# Sheet1.net
KiCad netlist of a schematic drawn in Altium Designer
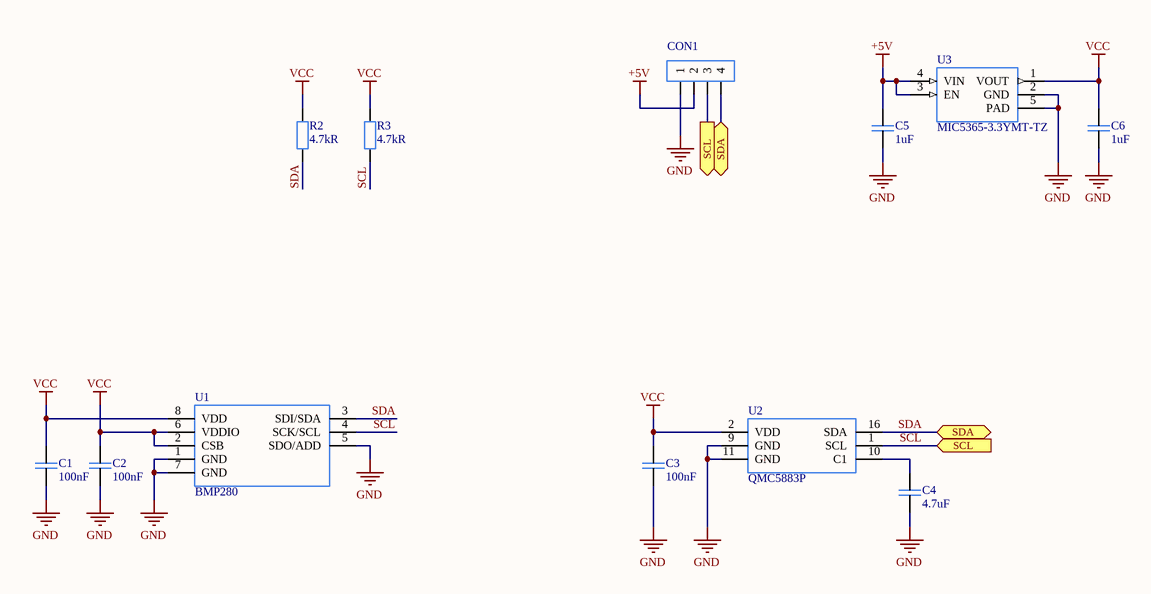
[diagram p0: Sheet1.SchDoc]

(export (version "E")
  (design (tool "Eeschema 10.0.6"))
  (components
    (comp (ref "C1")
      (value "100nF")
      (footprint "C0201_M")
      (description "Cap Ceramic 0.1uF 25V X5R 10% SMD 0201 85°C Paper T/R")
      (fields
        (field (name "MANUFACTURER") "Yageo")
        (field (name "MANUFACTURER PART NUMBER") "CC0201KRX5R8BB104")
      )
      (libsource (lib "Schlib1") (part "Capacitor"))
    )
    (comp (ref "C2")
      (value "100nF")
      (footprint "C0201_M")
      (description "Cap Ceramic 0.1uF 25V X5R 10% SMD 0201 85°C Paper T/R")
      (fields
        (field (name "MANUFACTURER") "Yageo")
        (field (name "MANUFACTURER PART NUMBER") "CC0201KRX5R8BB104")
      )
      (libsource (lib "Schlib1") (part "Capacitor"))
    )
    (comp (ref "C3")
      (value "100nF")
      (footprint "C0201_M")
      (description "Cap Ceramic 0.1uF 25V X5R 10% SMD 0201 85°C Paper T/R")
      (fields
        (field (name "MANUFACTURER") "Yageo")
        (field (name "MANUFACTURER PART NUMBER") "CC0201KRX5R8BB104")
      )
      (libsource (lib "Schlib1") (part "Capacitor"))
    )
    (comp (ref "C4")
      (value "4.7uF")
      (footprint "C0402_N")
      (description "贴片电容（MLCC） 0402")
      (fields
        (field (name "MANUFACTURER") "Taiyo Yuden")
        (field (name "MANUFACTURER PART NUMBER") "EDK105BBJ475MVLF")
      )
      (libsource (lib "Schlib1") (part "Capacitor"))
    )
    (comp (ref "C5")
      (value "1uF")
      (footprint "C0201_M")
      (description "Cap Cer 1UF 10V X5R 0201")
      (fields
        (field (name "MANUFACTURER") "Kyocera AVX")
        (field (name "MANUFACTURE PART NUMBER") "CM03X5R105M10AH")
      )
      (libsource (lib "Schlib1") (part "Capacitor"))
    )
    (comp (ref "C6")
      (value "1uF")
      (footprint "C0201_M")
      (description "Cap Cer 1UF 10V X5R 0201")
      (fields
        (field (name "MANUFACTURER") "Kyocera AVX")
        (field (name "MANUFACTURE PART NUMBER") "CM03X5R105M10AH")
      )
      (libsource (lib "Schlib1") (part "Capacitor"))
    )
    (comp (ref "CON1")
      (value "Header 4")
      (footprint "HEADER-4-2mm")
      (description "Connector; Header; 4pin")
      (libsource (lib "Schlib1") (part "HEADER1X4"))
    )
    (comp (ref "R2")
      (value "4.7kR")
      (footprint "R0201_L")
      (description "Res Thick Film 0201 4.7K Ohm 1% 1/20W ±200ppm/°C Molded SMD SMD Paper T/R")
      (fields
        (field (name "MANUFACTURER") "Yageo")
        (field (name "MANUFACTURER PART NUMBER") "RC0201FR-074K7L")
      )
      (libsource (lib "Schlib1") (part "Resistor_EU"))
    )
    (comp (ref "R3")
      (value "4.7kR")
      (footprint "R0201_L")
      (description "Res Thick Film 0201 4.7K Ohm 1% 1/20W ±200ppm/°C Molded SMD SMD Paper T/R")
      (fields
        (field (name "MANUFACTURER") "Yageo")
        (field (name "MANUFACTURER PART NUMBER") "RC0201FR-074K7L")
      )
      (libsource (lib "Schlib1") (part "Resistor_EU"))
    )
    (comp (ref "U1")
      (value "BMP280")
      (footprint "LGA-8")
      (description "SENSOR PRESSURE ABS")
      (fields (field (name "MANUFACTURER") "Bosch"))
      (libsource (lib "Schlib1") (part "BMP280"))
    )
    (comp (ref "U2")
      (value "QMC5883P")
      (footprint "LGA-16_3X3")
      (libsource (lib "Schlib1") (part "QMC5883P"))
    )
    (comp (ref "U3")
      (value "MIC5365-3.3YMT-TZ")
      (footprint "UDFN-4")
      (description "MIC5365 Series 3.3 V Fixed Output 150 mA Surface Mount LDO Regulator - TMLF-4")
      (fields (field (name "MANUFACTURER") "Microchip"))
      (libsource (lib "Schlib1") (part "MIC5365-3.3YMT-TZ"))
    )
  )
  (nets
    (net (code "1") (name "+5V") (class "Default")
      (node (ref "C5") (pin "1") (pinfunction "1_1") (pintype "passive"))
      (node (ref "CON1") (pin "2") (pinfunction "2_2") (pintype "passive"))
      (node (ref "U3") (pin "3") (pinfunction "EN_3") (pintype "input"))
      (node (ref "U3") (pin "4") (pinfunction "VIN_4") (pintype "input"))
    )
    (net (code "2") (name "/SCL") (class "Default")
      (node (ref "CON1") (pin "3") (pinfunction "3_3") (pintype "passive"))
      (node (ref "R3") (pin "2") (pintype "passive"))
      (node (ref "U1") (pin "4") (pinfunction "SCK/SCL_4") (pintype "passive"))
      (node (ref "U2") (pin "1") (pinfunction "SCL_1") (pintype "passive"))
    )
    (net (code "3") (name "/SDA") (class "Default")
      (node (ref "CON1") (pin "4") (pinfunction "4_4") (pintype "passive"))
      (node (ref "R2") (pin "2") (pintype "passive"))
      (node (ref "U1") (pin "3") (pinfunction "SDI/SDA_3") (pintype "passive"))
      (node (ref "U2") (pin "16") (pinfunction "SDA_16") (pintype "passive"))
    )
    (net (code "4") (name "GND") (class "Default")
      (node (ref "C1") (pin "2") (pinfunction "2_2") (pintype "passive"))
      (node (ref "C2") (pin "1") (pinfunction "1_1") (pintype "passive"))
      (node (ref "C3") (pin "1") (pinfunction "1_1") (pintype "passive"))
      (node (ref "C4") (pin "2") (pinfunction "2_2") (pintype "passive"))
      (node (ref "C5") (pin "2") (pinfunction "2_2") (pintype "passive"))
      (node (ref "C6") (pin "2") (pinfunction "2_2") (pintype "passive"))
      (node (ref "CON1") (pin "1") (pinfunction "1_1") (pintype "passive"))
      (node (ref "U1") (pin "1") (pinfunction "GND_1") (pintype "passive"))
      (node (ref "U1") (pin "5") (pinfunction "SDO/ADD_5") (pintype "passive"))
      (node (ref "U1") (pin "7") (pinfunction "GND_7") (pintype "passive"))
      (node (ref "U2") (pin "11") (pinfunction "GND_11") (pintype "passive"))
      (node (ref "U2") (pin "9") (pinfunction "GND_9") (pintype "passive"))
      (node (ref "U3") (pin "2") (pinfunction "GND_2") (pintype "power_in"))
      (node (ref "U3") (pin "5") (pinfunction "PAD_5") (pintype "passive"))
    )
    (net (code "5") (name "Net-(U2-C1)") (class "Default")
      (node (ref "C4") (pin "1") (pinfunction "1_1") (pintype "passive"))
      (node (ref "U2") (pin "10") (pinfunction "C1_10") (pintype "passive"))
    )
    (net (code "6") (name "VCC") (class "Default")
      (node (ref "C1") (pin "1") (pinfunction "1_1") (pintype "passive"))
      (node (ref "C2") (pin "2") (pinfunction "2_2") (pintype "passive"))
      (node (ref "C3") (pin "2") (pinfunction "2_2") (pintype "passive"))
      (node (ref "C6") (pin "1") (pinfunction "1_1") (pintype "passive"))
      (node (ref "R2") (pin "1") (pintype "passive"))
      (node (ref "R3") (pin "1") (pintype "passive"))
      (node (ref "U1") (pin "2") (pinfunction "CSB_2") (pintype "passive"))
      (node (ref "U1") (pin "6") (pinfunction "VDDIO_6") (pintype "passive"))
      (node (ref "U1") (pin "8") (pinfunction "VDD_8") (pintype "passive"))
      (node (ref "U2") (pin "2") (pinfunction "VDD_2") (pintype "passive"))
      (node (ref "U3") (pin "1") (pinfunction "VOUT_1") (pintype "output"))
    )
    (net (code "7") (name "unconnected-(U2-NC-Pad3)") (class "Default")
      (node (ref "U2") (pin "3") (pinfunction "NC_3") (pintype "passive"))
    )
    (net (code "8") (name "unconnected-(U2-NC-Pad4)") (class "Default")
      (node (ref "U2") (pin "4") (pinfunction "NC_4") (pintype "passive"))
    )
    (net (code "9") (name "unconnected-(U2-NC-Pad5)") (class "Default")
      (node (ref "U2") (pin "5") (pinfunction "NC_5") (pintype "passive"))
    )
    (net (code "10") (name "unconnected-(U2-NC-Pad6)") (class "Default")
      (node (ref "U2") (pin "6") (pinfunction "NC_6") (pintype "passive"))
    )
    (net (code "11") (name "unconnected-(U2-NC-Pad7)") (class "Default")
      (node (ref "U2") (pin "7") (pinfunction "NC_7") (pintype "passive"))
    )
    (net (code "12") (name "unconnected-(U2-NC-Pad8)") (class "Default")
      (node (ref "U2") (pin "8") (pinfunction "NC_8") (pintype "passive"))
    )
    (net (code "13") (name "unconnected-(U2-NC-Pad12)") (class "Default")
      (node (ref "U2") (pin "12") (pinfunction "NC_12") (pintype "passive"))
    )
    (net (code "14") (name "unconnected-(U2-NC-Pad13)") (class "Default")
      (node (ref "U2") (pin "13") (pinfunction "NC_13") (pintype "passive"))
    )
    (net (code "15") (name "unconnected-(U2-NC-Pad14)") (class "Default")
      (node (ref "U2") (pin "14") (pinfunction "NC_14") (pintype "passive"))
    )
    (net (code "16") (name "unconnected-(U2-NC-Pad15)") (class "Default")
      (node (ref "U2") (pin "15") (pinfunction "NC_15") (pintype "passive"))
    )
  )
)
